# Mako_DSP_QuadFlash_and_Boot.net
KiCad netlist of a schematic drawn in Altium Designer
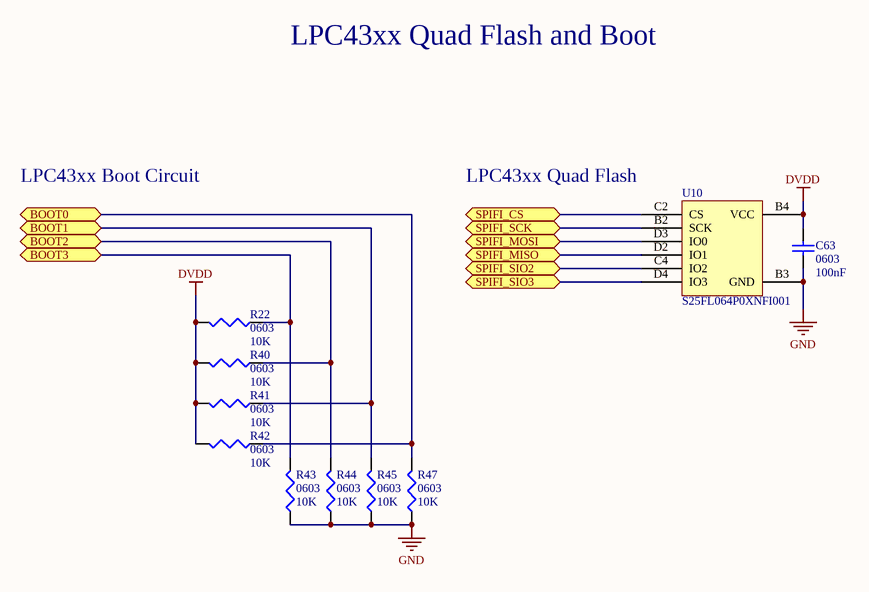
[diagram p0: Mako DSP QuadFlash and Boot.SchDoc]

(export (version "E")
  (design (tool "Eeschema 10.0.6"))
  (components
    (comp (ref "C63")
      (value "0603")
      (footprint "1608[0603]")
      (description "Capacitor (Semiconductor SIM Model)")
      (fields (field (name "ALTIUM_VALUE") "100nF") (field (name "PUBLISHER") "Altium Limited"))
      (libsource (lib "Miscellaneous Devices") (part "Cap Semi"))
    )
    (comp (ref "R22")
      (value "0603")
      (footprint "J1-0603")
      (description "Resistor")
      (fields (field (name "ALTIUM_VALUE") "10K") (field (name "PUBLISHER") "Altium Limited"))
      (libsource (lib "Miscellaneous Devices") (part "Res3"))
    )
    (comp (ref "R40")
      (value "0603")
      (footprint "J1-0603")
      (description "Resistor")
      (fields (field (name "ALTIUM_VALUE") "10K") (field (name "PUBLISHER") "Altium Limited"))
      (libsource (lib "Miscellaneous Devices") (part "Res3"))
    )
    (comp (ref "R41")
      (value "0603")
      (footprint "J1-0603")
      (description "Resistor")
      (fields (field (name "ALTIUM_VALUE") "10K") (field (name "PUBLISHER") "Altium Limited"))
      (libsource (lib "Miscellaneous Devices") (part "Res3"))
    )
    (comp (ref "R42")
      (value "0603")
      (footprint "J1-0603")
      (description "Resistor")
      (fields (field (name "ALTIUM_VALUE") "10K") (field (name "PUBLISHER") "Altium Limited"))
      (libsource (lib "Miscellaneous Devices") (part "Res3"))
    )
    (comp (ref "R43")
      (value "0603")
      (footprint "J1-0603")
      (description "Resistor")
      (fields (field (name "ALTIUM_VALUE") "10K") (field (name "PUBLISHER") "Altium Limited"))
      (libsource (lib "Miscellaneous Devices") (part "Res3"))
    )
    (comp (ref "R44")
      (value "0603")
      (footprint "J1-0603")
      (description "Resistor")
      (fields (field (name "ALTIUM_VALUE") "10K") (field (name "PUBLISHER") "Altium Limited"))
      (libsource (lib "Miscellaneous Devices") (part "Res3"))
    )
    (comp (ref "R45")
      (value "0603")
      (footprint "J1-0603")
      (description "Resistor")
      (fields (field (name "ALTIUM_VALUE") "10K") (field (name "PUBLISHER") "Altium Limited"))
      (libsource (lib "Miscellaneous Devices") (part "Res3"))
    )
    (comp (ref "R47")
      (value "0603")
      (footprint "J1-0603")
      (description "Resistor")
      (fields (field (name "ALTIUM_VALUE") "10K") (field (name "PUBLISHER") "Altium Limited"))
      (libsource (lib "Miscellaneous Devices") (part "Res3"))
    )
    (comp (ref "U10")
      (value "S25FL064P0XNFI001")
      (footprint "S25FL064P0XNFI001")
      (description "SPIFI Quad Flash")
      (libsource (lib "Mako DSP Schematic Library") (part "S25FL064P0XNFI001"))
    )
  )
  (nets
    (net (code "1") (name "/BOOT0") (class "Default")
      (node (ref "R42") (pin "1") (pinfunction "1_1") (pintype "passive"))
      (node (ref "R47") (pin "2") (pinfunction "2_2") (pintype "passive"))
    )
    (net (code "2") (name "/BOOT1") (class "Default")
      (node (ref "R41") (pin "1") (pinfunction "1_1") (pintype "passive"))
      (node (ref "R45") (pin "2") (pinfunction "2_2") (pintype "passive"))
    )
    (net (code "3") (name "/BOOT2") (class "Default")
      (node (ref "R40") (pin "1") (pinfunction "1_1") (pintype "passive"))
      (node (ref "R44") (pin "2") (pinfunction "2_2") (pintype "passive"))
    )
    (net (code "4") (name "/BOOT3") (class "Default")
      (node (ref "R22") (pin "1") (pinfunction "1_1") (pintype "passive"))
      (node (ref "R43") (pin "2") (pinfunction "2_2") (pintype "passive"))
    )
    (net (code "5") (name "/SPIFI_CS") (class "Default")
      (node (ref "U10") (pin "C2") (pinfunction "CS_C2") (pintype "passive"))
    )
    (net (code "6") (name "/SPIFI_MISO") (class "Default")
      (node (ref "U10") (pin "D2") (pinfunction "IO1_D2") (pintype "passive"))
    )
    (net (code "7") (name "/SPIFI_MOSI") (class "Default")
      (node (ref "U10") (pin "D3") (pinfunction "IO0_D3") (pintype "passive"))
    )
    (net (code "8") (name "/SPIFI_SCK") (class "Default")
      (node (ref "U10") (pin "B2") (pinfunction "SCK_B2") (pintype "passive"))
    )
    (net (code "9") (name "/SPIFI_SIO2") (class "Default")
      (node (ref "U10") (pin "C4") (pinfunction "IO2_C4") (pintype "passive"))
    )
    (net (code "10") (name "/SPIFI_SIO3") (class "Default")
      (node (ref "U10") (pin "D4") (pinfunction "IO3_D4") (pintype "passive"))
    )
    (net (code "11") (name "DVDD") (class "Default")
      (node (ref "C63") (pin "2") (pinfunction "2_2") (pintype "passive"))
      (node (ref "R22") (pin "2") (pinfunction "2_2") (pintype "passive"))
      (node (ref "R40") (pin "2") (pinfunction "2_2") (pintype "passive"))
      (node (ref "R41") (pin "2") (pinfunction "2_2") (pintype "passive"))
      (node (ref "R42") (pin "2") (pinfunction "2_2") (pintype "passive"))
      (node (ref "U10") (pin "B4") (pinfunction "VCC_B4") (pintype "passive"))
    )
    (net (code "12") (name "GND") (class "Default")
      (node (ref "C63") (pin "1") (pinfunction "1_1") (pintype "passive"))
      (node (ref "R43") (pin "1") (pinfunction "1_1") (pintype "passive"))
      (node (ref "R44") (pin "1") (pinfunction "1_1") (pintype "passive"))
      (node (ref "R45") (pin "1") (pinfunction "1_1") (pintype "passive"))
      (node (ref "R47") (pin "1") (pinfunction "1_1") (pintype "passive"))
      (node (ref "U10") (pin "B3") (pinfunction "GND_B3") (pintype "passive"))
    )
    (net (code "13") (name "unconnected-(U10-NC-PadA2)") (class "Default")
      (node (ref "U10") (pin "A2") (pinfunction "NC_A2") (pintype "passive"))
    )
    (net (code "14") (name "unconnected-(U10-NC-PadA3)") (class "Default")
      (node (ref "U10") (pin "A3") (pinfunction "NC_A3") (pintype "passive"))
    )
    (net (code "15") (name "unconnected-(U10-NC-PadA4)") (class "Default")
      (node (ref "U10") (pin "A4") (pinfunction "NC_A4") (pintype "passive"))
    )
    (net (code "16") (name "unconnected-(U10-NC-PadA5)") (class "Default")
      (node (ref "U10") (pin "A5") (pinfunction "NC_A5") (pintype "passive"))
    )
    (net (code "17") (name "unconnected-(U10-NC-PadB1)") (class "Default")
      (node (ref "U10") (pin "B1") (pinfunction "NC_B1") (pintype "passive"))
    )
    (net (code "18") (name "unconnected-(U10-NC-PadB5)") (class "Default")
      (node (ref "U10") (pin "B5") (pinfunction "NC_B5") (pintype "passive"))
    )
    (net (code "19") (name "unconnected-(U10-NC-PadC1)") (class "Default")
      (node (ref "U10") (pin "C1") (pinfunction "NC_C1") (pintype "passive"))
    )
    (net (code "20") (name "unconnected-(U10-NC-PadC5)") (class "Default")
      (node (ref "U10") (pin "C5") (pinfunction "NC_C5") (pintype "passive"))
    )
    (net (code "21") (name "unconnected-(U10-NC-PadD1)") (class "Default")
      (node (ref "U10") (pin "D1") (pinfunction "NC_D1") (pintype "passive"))
    )
    (net (code "22") (name "unconnected-(U10-NC-PadD5)") (class "Default")
      (node (ref "U10") (pin "D5") (pinfunction "NC_D5") (pintype "passive"))
    )
    (net (code "23") (name "unconnected-(U10-NC-PadE1)") (class "Default")
      (node (ref "U10") (pin "E1") (pinfunction "NC_E1") (pintype "passive"))
    )
    (net (code "24") (name "unconnected-(U10-NC-PadE2)") (class "Default")
      (node (ref "U10") (pin "E2") (pinfunction "NC_E2") (pintype "passive"))
    )
    (net (code "25") (name "unconnected-(U10-NC-PadE3)") (class "Default")
      (node (ref "U10") (pin "E3") (pinfunction "NC_E3") (pintype "passive"))
    )
    (net (code "26") (name "unconnected-(U10-NC-PadE4)") (class "Default")
      (node (ref "U10") (pin "E4") (pinfunction "NC_E4") (pintype "passive"))
    )
    (net (code "27") (name "unconnected-(U10-NC-PadE5)") (class "Default")
      (node (ref "U10") (pin "E5") (pinfunction "NC_E5") (pintype "passive"))
    )
  )
)
